# SCH_LED-Blinker_2026-03-04.net
KiCad netlist of a schematic drawn in EasyEDA
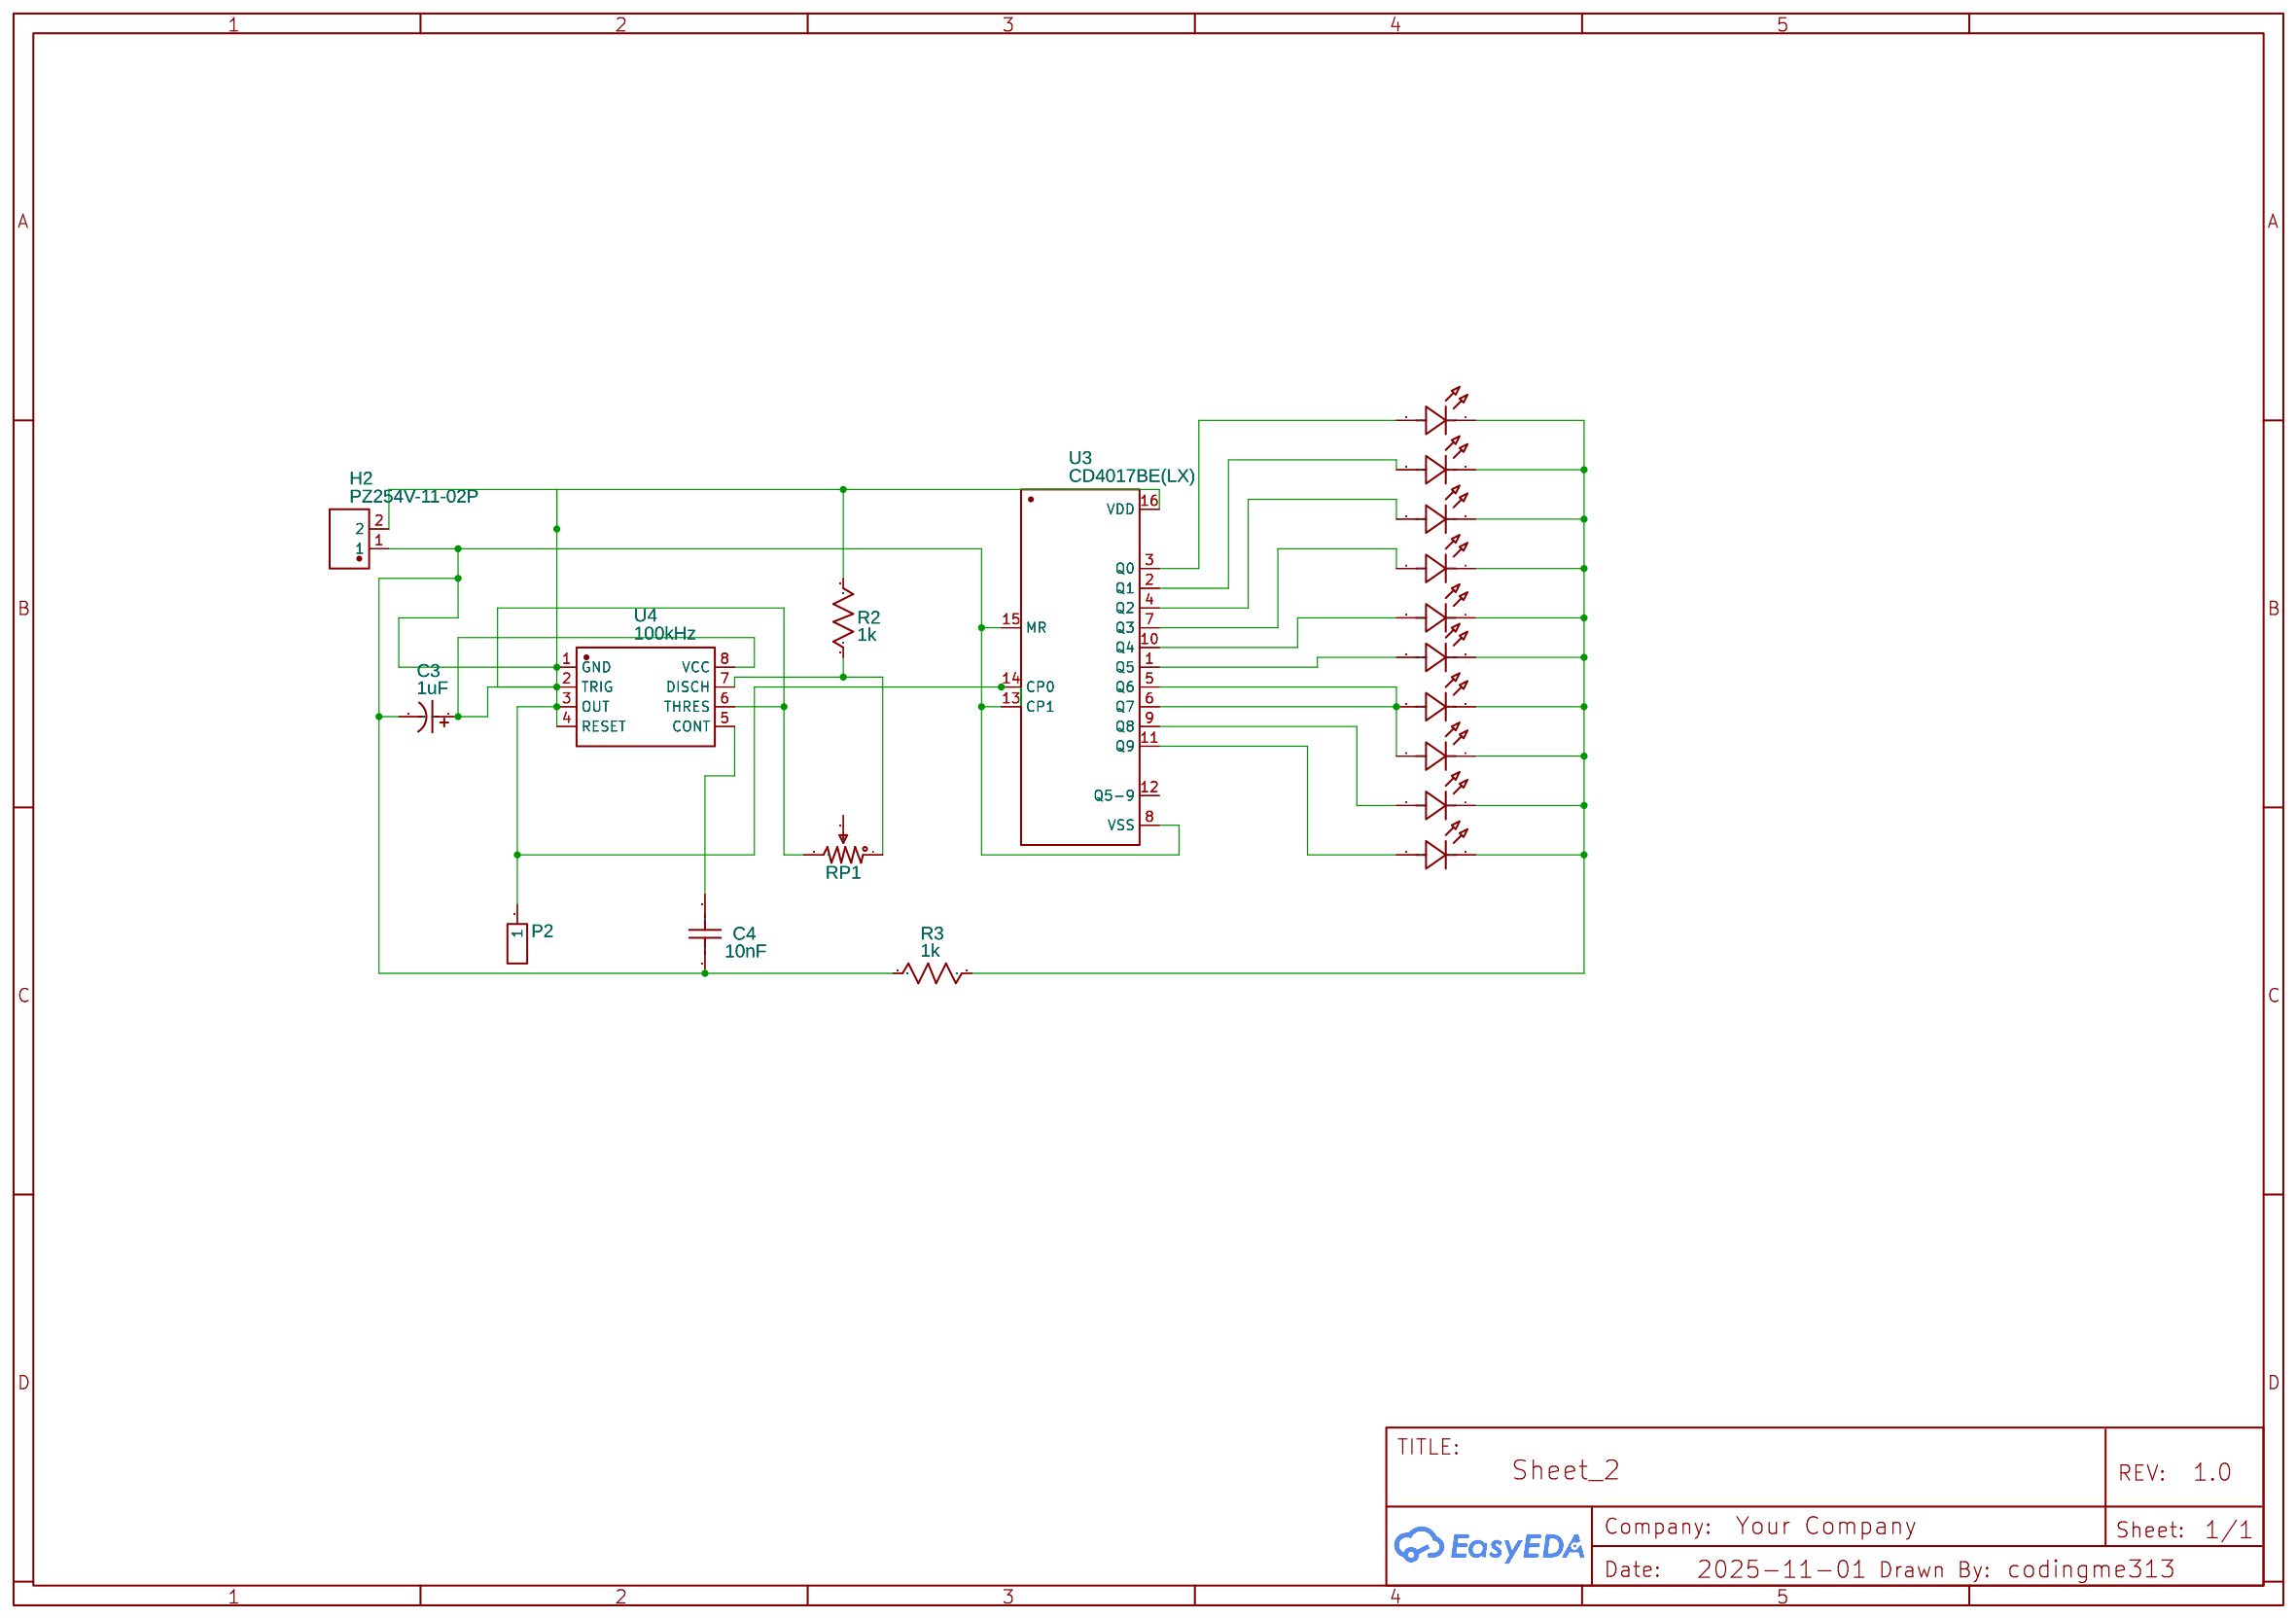
[diagram p0: schematic sheet]

(export (version "E")
  (design (tool "Eeschema 10.0.6"))
  (components
    (comp (ref "C3")
      (value "1uF")
      (fields (field (name "Manufacturer Part") "KF010M050C110A") (field (name "Manufacturer") "CapXon(丰宾)"))
      (libsource (lib "") (part "KF010M050C110A"))
    )
    (comp (ref "C4")
      (value "10nF")
      (fields (field (name "Manufacturer Part") "N09F1B103MN0B0S0N0") (field (name "Manufacturer") "STE(松田)"))
      (libsource (lib "") (part "N09F1B103MN0B0S0N0"))
    )
    (comp (ref "H2")
      (value "PZ254V-11-02P")
      (fields (field (name "Manufacturer") "XFCN(兴飞)"))
      (libsource (lib "") (part "PZ254V-11-02P"))
    )
    (comp (ref "LED1")
      (value "XL-502UWC")
      (fields (field (name "Manufacturer") "XINGLIGHT(成兴光)"))
      (libsource (lib "") (part "XL-502UWC"))
    )
    (comp (ref "LED2")
      (value "XL-502UWC")
      (fields (field (name "Manufacturer") "XINGLIGHT(成兴光)"))
      (libsource (lib "") (part "XL-502UWC"))
    )
    (comp (ref "LED3")
      (value "XL-502UWC")
      (fields (field (name "Manufacturer") "XINGLIGHT(成兴光)"))
      (libsource (lib "") (part "XL-502UWC"))
    )
    (comp (ref "LED4")
      (value "XL-502UWC")
      (fields (field (name "Manufacturer") "XINGLIGHT(成兴光)"))
      (libsource (lib "") (part "XL-502UWC"))
    )
    (comp (ref "LED5")
      (value "XL-502UWC")
      (fields (field (name "Manufacturer") "XINGLIGHT(成兴光)"))
      (libsource (lib "") (part "XL-502UWC"))
    )
    (comp (ref "LED6")
      (value "XL-502UWC")
      (fields (field (name "Manufacturer") "XINGLIGHT(成兴光)"))
      (libsource (lib "") (part "XL-502UWC"))
    )
    (comp (ref "LED7")
      (value "XL-502UWC")
      (fields (field (name "Manufacturer") "XINGLIGHT(成兴光)"))
      (libsource (lib "") (part "XL-502UWC"))
    )
    (comp (ref "LED8")
      (value "XL-502UWC")
      (fields (field (name "Manufacturer") "XINGLIGHT(成兴光)"))
      (libsource (lib "") (part "XL-502UWC"))
    )
    (comp (ref "LED9")
      (value "XL-502UWC")
      (fields (field (name "Manufacturer") "XINGLIGHT(成兴光)"))
      (libsource (lib "") (part "XL-502UWC"))
    )
    (comp (ref "LED12")
      (value "XL-502UWC")
      (fields (field (name "Manufacturer") "XINGLIGHT(成兴光)"))
      (libsource (lib "") (part "XL-502UWC"))
    )
    (comp (ref "P2")
      (value "Header-Male-2.54_1x1")
      (fields (field (name "Manufacturer Part") "2.54-1*1P针") (field (name "Manufacturer") "BOOMELE(博穆精密)"))
      (libsource (lib "") (part "Header-Male-2.54_1x1"))
    )
    (comp (ref "R2") (value "1k") (libsource (lib "") (part "R_0603_US_1")))
    (comp (ref "R3") (value "1k") (libsource (lib "") (part "R_0603_US")))
    (comp (ref "RP1") (value "R_3386P_US") (libsource (lib "") (part "R_3386P_US")))
    (comp (ref "U3")
      (value "CD4017BE(LX)")
      (fields (field (name "Manufacturer") "LX(灵星芯微)"))
      (libsource (lib "") (part "CD4017BE(LX)"))
    )
    (comp (ref "U4")
      (value "100kHz")
      (fields (field (name "Manufacturer Part") "NE555P") (field (name "Manufacturer") "TI(德州仪器)"))
      (libsource (lib "") (part "NE555P"))
    )
  )
  (nets
    (net (code "1") (name "Net-(LED1-A)") (class "Default")
      (node (ref "LED1") (pin "2") (pinfunction "A_2") (pintype "unspecified"))
      (node (ref "U3") (pin "2") (pinfunction "Q1_2") (pintype "unspecified"))
    )
    (net (code "2") (name "Net-(LED1-K)") (class "Default")
      (node (ref "LED1") (pin "1") (pinfunction "K_1") (pintype "unspecified"))
      (node (ref "LED12") (pin "1") (pinfunction "K_1") (pintype "unspecified"))
      (node (ref "LED2") (pin "1") (pinfunction "K_1") (pintype "unspecified"))
      (node (ref "LED3") (pin "1") (pinfunction "K_1") (pintype "unspecified"))
      (node (ref "LED4") (pin "1") (pinfunction "K_1") (pintype "unspecified"))
      (node (ref "LED5") (pin "1") (pinfunction "K_1") (pintype "unspecified"))
      (node (ref "LED6") (pin "1") (pinfunction "K_1") (pintype "unspecified"))
      (node (ref "LED7") (pin "1") (pinfunction "K_1") (pintype "unspecified"))
      (node (ref "LED8") (pin "1") (pinfunction "K_1") (pintype "unspecified"))
      (node (ref "LED9") (pin "1") (pinfunction "K_1") (pintype "unspecified"))
      (node (ref "R3") (pin "1") (pinfunction "1_1") (pintype "unspecified"))
    )
    (net (code "3") (name "Net-(LED2-A)") (class "Default")
      (node (ref "LED2") (pin "2") (pinfunction "A_2") (pintype "unspecified"))
      (node (ref "U3") (pin "4") (pinfunction "Q2_4") (pintype "unspecified"))
    )
    (net (code "4") (name "Net-(LED3-A)") (class "Default")
      (node (ref "LED3") (pin "2") (pinfunction "A_2") (pintype "unspecified"))
      (node (ref "U3") (pin "7") (pinfunction "Q3_7") (pintype "unspecified"))
    )
    (net (code "5") (name "Net-(LED4-A)") (class "Default")
      (node (ref "LED4") (pin "2") (pinfunction "A_2") (pintype "unspecified"))
      (node (ref "U3") (pin "10") (pinfunction "Q4_10") (pintype "unspecified"))
    )
    (net (code "6") (name "Net-(LED5-A)") (class "Default")
      (node (ref "LED5") (pin "2") (pinfunction "A_2") (pintype "unspecified"))
      (node (ref "U3") (pin "1") (pinfunction "Q5_1") (pintype "unspecified"))
    )
    (net (code "7") (name "Net-(LED6-A)") (class "Default")
      (node (ref "LED6") (pin "2") (pinfunction "A_2") (pintype "unspecified"))
      (node (ref "LED7") (pin "2") (pinfunction "A_2") (pintype "unspecified"))
      (node (ref "U3") (pin "5") (pinfunction "Q6_5") (pintype "unspecified"))
      (node (ref "U3") (pin "6") (pinfunction "Q7_6") (pintype "unspecified"))
    )
    (net (code "8") (name "Net-(LED8-A)") (class "Default")
      (node (ref "LED8") (pin "2") (pinfunction "A_2") (pintype "unspecified"))
      (node (ref "U3") (pin "9") (pinfunction "Q8_9") (pintype "unspecified"))
    )
    (net (code "9") (name "Net-(LED9-A)") (class "Default")
      (node (ref "LED9") (pin "2") (pinfunction "A_2") (pintype "unspecified"))
      (node (ref "U3") (pin "11") (pinfunction "Q9_11") (pintype "unspecified"))
    )
    (net (code "10") (name "Net-(LED12-A)") (class "Default")
      (node (ref "LED12") (pin "2") (pinfunction "A_2") (pintype "unspecified"))
      (node (ref "U3") (pin "3") (pinfunction "Q0_3") (pintype "unspecified"))
    )
    (net (code "11") (name "Net-(U3-CP0)") (class "Default")
      (node (ref "C3") (pin "1") (pinfunction "1_1") (pintype "input"))
      (node (ref "C3") (pin "2") (pinfunction "2_2") (pintype "input"))
      (node (ref "C4") (pin "1") (pinfunction "1_1") (pintype "unspecified"))
      (node (ref "H2") (pin "1") (pinfunction "1_1") (pintype "unspecified"))
      (node (ref "H2") (pin "2") (pinfunction "2_2") (pintype "unspecified"))
      (node (ref "P2") (pin "1") (pinfunction "1_1") (pintype "input"))
      (node (ref "R2") (pin "2") (pinfunction "2_2") (pintype "unspecified"))
      (node (ref "R3") (pin "2") (pinfunction "2_2") (pintype "unspecified"))
      (node (ref "RP1") (pin "3") (pinfunction "3_3") (pintype "unspecified"))
      (node (ref "U3") (pin "13") (pinfunction "CP1_13") (pintype "unspecified"))
      (node (ref "U3") (pin "14") (pinfunction "CP0_14") (pintype "unspecified"))
      (node (ref "U3") (pin "15") (pinfunction "MR_15") (pintype "unspecified"))
      (node (ref "U3") (pin "16") (pinfunction "VDD_16") (pintype "unspecified"))
      (node (ref "U3") (pin "8") (pinfunction "VSS_8") (pintype "unspecified"))
      (node (ref "U4") (pin "1") (pinfunction "GND_1") (pintype "unspecified"))
      (node (ref "U4") (pin "2") (pinfunction "TRIG_2") (pintype "unspecified"))
      (node (ref "U4") (pin "3") (pinfunction "OUT_3") (pintype "unspecified"))
      (node (ref "U4") (pin "4") (pinfunction "RESET_4") (pintype "unspecified"))
      (node (ref "U4") (pin "6") (pinfunction "THRES_6") (pintype "unspecified"))
      (node (ref "U4") (pin "8") (pinfunction "VCC_8") (pintype "unspecified"))
    )
    (net (code "12") (name "Net-(U4-CONT)") (class "Default")
      (node (ref "C4") (pin "2") (pinfunction "2_2") (pintype "unspecified"))
      (node (ref "U4") (pin "5") (pinfunction "CONT_5") (pintype "unspecified"))
    )
    (net (code "13") (name "Net-(U4-DISCH)") (class "Default")
      (node (ref "R2") (pin "1") (pinfunction "1_1") (pintype "unspecified"))
      (node (ref "RP1") (pin "1") (pinfunction "1_1") (pintype "unspecified"))
      (node (ref "U4") (pin "7") (pinfunction "DISCH_7") (pintype "unspecified"))
    )
    (net (code "14") (name "unconnected-(RP1-Pad2)") (class "Default")
      (node (ref "RP1") (pin "2") (pinfunction "2_2") (pintype "unspecified"))
    )
    (net (code "15") (name "unconnected-(U3-Q5-9-Pad12)") (class "Default")
      (node (ref "U3") (pin "12") (pinfunction "Q5-9_12") (pintype "unspecified"))
    )
  )
)
